# MTRduino_rev5_2.net
KiCad netlist of a schematic drawn in EAGLE
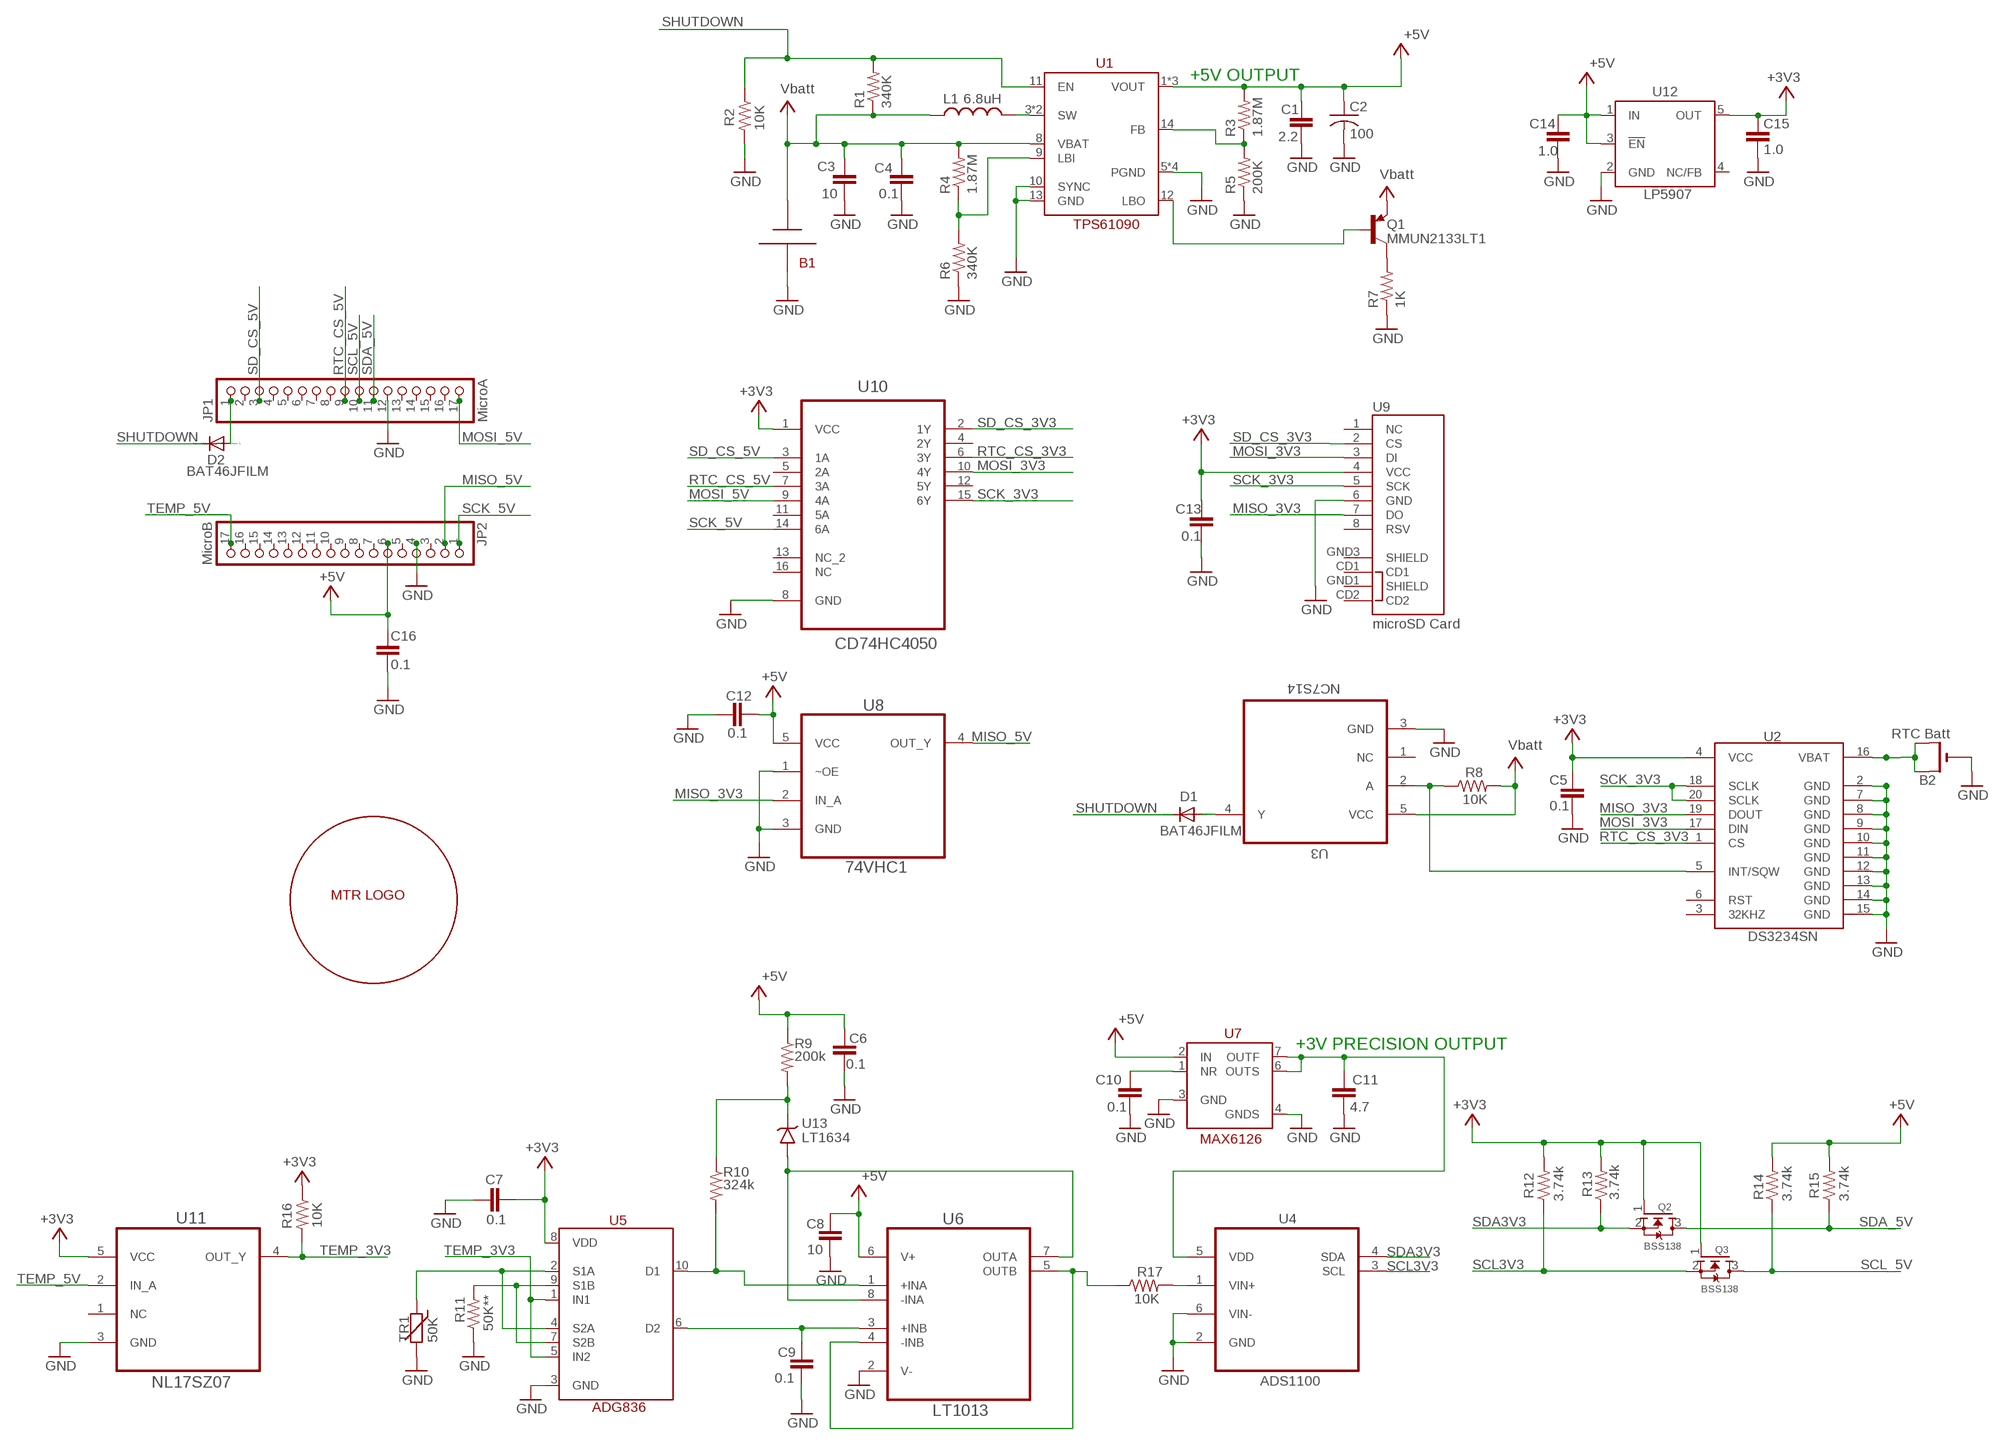
[diagram p0: schematic, sheet 1]

(export (version "E")
  (design (tool "Eeschema 10.0.6"))
  (components
    (comp (ref "B1")
      (value "2x AA BATT")
      (footprint "eagle-import:BATT_AA2")
      (libsource (lib "eagle-import") (part "BATT_AA2"))
    )
    (comp (ref "B2")
      (value "RTC Batt")
      (footprint "eagle-import:CR1220-SMD")
      (libsource (lib "eagle-import") (part "CR1220SMT"))
    )
    (comp (ref "C1")
      (value "2.2")
      (footprint "eagle-import:C0603")
      (libsource (lib "eagle-import") (part "C-EUC0603"))
    )
    (comp (ref "C2")
      (value "100")
      (footprint "eagle-import:C1206K")
      (libsource (lib "eagle-import") (part "C-USC1206K"))
    )
    (comp (ref "C3")
      (value "10")
      (footprint "eagle-import:C0603")
      (libsource (lib "eagle-import") (part "C-EUC0603"))
    )
    (comp (ref "C4")
      (value "0.1")
      (footprint "eagle-import:C0603")
      (libsource (lib "eagle-import") (part "C-EUC0603"))
    )
    (comp (ref "C5")
      (value "0.1")
      (footprint "eagle-import:C0603")
      (libsource (lib "eagle-import") (part "C-EUC0603"))
    )
    (comp (ref "C6")
      (value "0.1")
      (footprint "eagle-import:C0603")
      (libsource (lib "eagle-import") (part "C-EUC0603"))
    )
    (comp (ref "C7")
      (value "0.1")
      (footprint "eagle-import:C0603")
      (libsource (lib "eagle-import") (part "C-EUC0603"))
    )
    (comp (ref "C8")
      (value "10")
      (footprint "eagle-import:C0603")
      (libsource (lib "eagle-import") (part "C-EUC0603"))
    )
    (comp (ref "C9")
      (value "0.1")
      (footprint "eagle-import:C0603")
      (libsource (lib "eagle-import") (part "C-EUC0603"))
    )
    (comp (ref "C10")
      (value "0.1")
      (footprint "eagle-import:C0603")
      (libsource (lib "eagle-import") (part "C-EUC0603"))
    )
    (comp (ref "C11")
      (value "4.7")
      (footprint "eagle-import:C0603")
      (libsource (lib "eagle-import") (part "C-EUC0603"))
    )
    (comp (ref "C12")
      (value "0.1")
      (footprint "eagle-import:C0603")
      (libsource (lib "eagle-import") (part "C-EUC0603"))
    )
    (comp (ref "C13")
      (value "0.1")
      (footprint "eagle-import:C0603")
      (libsource (lib "eagle-import") (part "C-EUC0603"))
    )
    (comp (ref "C14")
      (value "1.0")
      (footprint "eagle-import:C0603")
      (libsource (lib "eagle-import") (part "C-EUC0603"))
    )
    (comp (ref "C15")
      (value "1.0")
      (footprint "eagle-import:C0603")
      (libsource (lib "eagle-import") (part "C-EUC0603"))
    )
    (comp (ref "C16")
      (value "0.1")
      (footprint "eagle-import:C0603")
      (libsource (lib "eagle-import") (part "C-EUC0603"))
    )
    (comp (ref "D1")
      (value "BAT46JFILM")
      (footprint "eagle-import:SOD323-R")
      (libsource (lib "eagle-import") (part "DIODE-SOD323-R"))
    )
    (comp (ref "D2")
      (value "BAT46JFILM")
      (footprint "eagle-import:SOD323-R")
      (libsource (lib "eagle-import") (part "DIODE-SOD323-R"))
    )
    (comp (ref "JP1")
      (value "MicroA")
      (footprint "eagle-import:1X17")
      (libsource (lib "eagle-import") (part "PINHD-1X17"))
    )
    (comp (ref "JP2")
      (value "MicroB")
      (footprint "eagle-import:1X17")
      (libsource (lib "eagle-import") (part "PINHD-1X17"))
    )
    (comp (ref "L1")
      (value "6.8uH")
      (footprint "eagle-import:VLC6045")
      (libsource (lib "eagle-import") (part "L-USVLC6045"))
    )
    (comp (ref "Q1")
      (value "MMUN2133LT1")
      (footprint "eagle-import:SC59-BEC")
      (libsource (lib "eagle-import") (part "MMUN2111LT1"))
    )
    (comp (ref "Q2")
      (value "BSS138")
      (footprint "eagle-import:SOT23")
      (libsource (lib "eagle-import") (part "MOSFET-NREFLOW"))
    )
    (comp (ref "Q3")
      (value "BSS138")
      (footprint "eagle-import:SOT23")
      (libsource (lib "eagle-import") (part "MOSFET-NREFLOW"))
    )
    (comp (ref "R1")
      (value "340K")
      (footprint "eagle-import:R0603")
      (libsource (lib "eagle-import") (part "R-US_R0603"))
    )
    (comp (ref "R2")
      (value "10K")
      (footprint "eagle-import:R0603")
      (libsource (lib "eagle-import") (part "R-US_R0603"))
    )
    (comp (ref "R3")
      (value "1.87M")
      (footprint "eagle-import:R0805")
      (libsource (lib "eagle-import") (part "R-US_R0805"))
    )
    (comp (ref "R4")
      (value "1.87M")
      (footprint "eagle-import:R0805")
      (libsource (lib "eagle-import") (part "R-US_R0805"))
    )
    (comp (ref "R5")
      (value "200K")
      (footprint "eagle-import:R0603")
      (libsource (lib "eagle-import") (part "R-US_R0603"))
    )
    (comp (ref "R6")
      (value "340K")
      (footprint "eagle-import:R0603")
      (libsource (lib "eagle-import") (part "R-US_R0603"))
    )
    (comp (ref "R7")
      (value "1K")
      (footprint "eagle-import:R0603")
      (libsource (lib "eagle-import") (part "R-US_R0603"))
    )
    (comp (ref "R8")
      (value "10K")
      (footprint "eagle-import:R0603")
      (libsource (lib "eagle-import") (part "R-US_R0603"))
    )
    (comp (ref "R9")
      (value "200k")
      (footprint "eagle-import:R1206")
      (libsource (lib "eagle-import") (part "R-US_R1206"))
    )
    (comp (ref "R10")
      (value "324k")
      (footprint "eagle-import:R1206")
      (libsource (lib "eagle-import") (part "R-US_R1206"))
    )
    (comp (ref "R11")
      (value "50K**")
      (footprint "eagle-import:R2010")
      (libsource (lib "eagle-import") (part "R-US_R2010"))
    )
    (comp (ref "R12")
      (value "3.74k")
      (footprint "eagle-import:R0603")
      (libsource (lib "eagle-import") (part "R-US_R0603"))
    )
    (comp (ref "R13")
      (value "3.74k")
      (footprint "eagle-import:R0603")
      (libsource (lib "eagle-import") (part "R-US_R0603"))
    )
    (comp (ref "R14")
      (value "3.74k")
      (footprint "eagle-import:R0603")
      (libsource (lib "eagle-import") (part "R-US_R0603"))
    )
    (comp (ref "R15")
      (value "3.74k")
      (footprint "eagle-import:R0603")
      (libsource (lib "eagle-import") (part "R-US_R0603"))
    )
    (comp (ref "R16")
      (value "10K")
      (footprint "eagle-import:R0603")
      (libsource (lib "eagle-import") (part "R-US_R0603"))
    )
    (comp (ref "R17")
      (value "10K")
      (footprint "eagle-import:R0603")
      (libsource (lib "eagle-import") (part "R-US_R0603"))
    )
    (comp (ref "TR1")
      (value "50K")
      (footprint "eagle-import:R-5")
      (libsource (lib "eagle-import") (part "THERMISTOR_R-5"))
    )
    (comp (ref "U$1")
      (value "MTRLOGO")
      (footprint "eagle-import:MTRLOGO")
      (libsource (lib "eagle-import") (part "MTRLOGO"))
    )
    (comp (ref "U1")
      (value "TPS61090")
      (footprint "eagle-import:QFN16-4X4")
      (libsource (lib "eagle-import") (part "TPS61090RSAR"))
    )
    (comp (ref "U2")
      (value "DS3234SN")
      (footprint "eagle-import:DS3234")
      (libsource (lib "eagle-import") (part "DS3234"))
    )
    (comp (ref "U3")
      (value "NC7S14")
      (footprint "eagle-import:SOT95P280X145-5N")
      (fields (field (name "MPN") "1P1G14MDBVREPG4"))
      (libsource (lib "eagle-import") (part "1P1G14MDBVREPG4"))
    )
    (comp (ref "U4")
      (value "ADS1100")
      (footprint "eagle-import:SOT95P280X145-6N")
      (fields (field (name "MPN") "ADS1100A0IDBVT"))
      (libsource (lib "eagle-import") (part "ADS1100A0IDBVT"))
    )
    (comp (ref "U5")
      (value "ADG836")
      (footprint "eagle-import:MSOP10")
      (libsource (lib "eagle-import") (part "ADG836"))
    )
    (comp (ref "U6")
      (value "LT1013")
      (footprint "eagle-import:SOIC127P600X175-8N")
      (fields (field (name "MPN") "LT1013DS8#PBF"))
      (libsource (lib "eagle-import") (part "LT1013DS8PBF"))
    )
    (comp (ref "U7")
      (value "MAX6126")
      (footprint "eagle-import:SOIC127P600X175-8N")
      (libsource (lib "eagle-import") (part "MAX6126"))
    )
    (comp (ref "U8")
      (value "74VHC1")
      (footprint "eagle-import:SOT65P210X110-5N")
      (fields (field (name "MPN") "M74VHC1GT125DF1G"))
      (libsource (lib "eagle-import") (part "M74VHC1GT125DF1G"))
    )
    (comp (ref "U9")
      (value "microSD Card")
      (footprint "eagle-import:MICROSD_1_1")
      (libsource (lib "eagle-import") (part "USD-SOCKET"))
    )
    (comp (ref "U10")
      (value "CD74HC4050")
      (footprint "eagle-import:SOIC127P600X175-16N")
      (fields (field (name "MPN") "M74HC4050RM13TR"))
      (libsource (lib "eagle-import") (part "M74HC4050RM13TR"))
    )
    (comp (ref "U11")
      (value "NL17SZ07")
      (footprint "eagle-import:SOT65P210X110-5N")
      (fields (field (name "MPN") "NL17SZ07DFT2G"))
      (libsource (lib "eagle-import") (part "NL17SZ07DFT2G"))
    )
    (comp (ref "U12")
      (value "LP5907")
      (footprint "eagle-import:SOT23-DBV")
      (fields (field (name "MF") "TEXAS INSTRUMENTS") (field (name "MPN") "TPS77030DBVT"))
      (libsource (lib "eagle-import") (part "TPS77030"))
    )
    (comp (ref "U13")
      (value "LT1634")
      (footprint "eagle-import:S8")
      (libsource (lib "eagle-import") (part "LT1634BIS8-1.25"))
    )
  )
  (nets
    (net (code "1") (name "+3V3") (class "Default")
      (node (ref "C13") (pin "1") (pinfunction "1_1") (pintype "passive"))
      (node (ref "C15") (pin "1") (pinfunction "1_1") (pintype "passive"))
      (node (ref "C5") (pin "1") (pinfunction "1_1") (pintype "passive"))
      (node (ref "C7") (pin "2") (pinfunction "2_2") (pintype "passive"))
      (node (ref "Q2") (pin "1") (pinfunction "G_1") (pintype "bidirectional"))
      (node (ref "Q3") (pin "1") (pinfunction "G_1") (pintype "bidirectional"))
      (node (ref "R12") (pin "2") (pinfunction "2_2") (pintype "passive"))
      (node (ref "R13") (pin "2") (pinfunction "2_2") (pintype "passive"))
      (node (ref "R16") (pin "1") (pinfunction "1_1") (pintype "passive"))
      (node (ref "U10") (pin "1") (pinfunction "VCC_1") (pintype "power_in"))
      (node (ref "U11") (pin "5") (pinfunction "VCC_5") (pintype "power_in"))
      (node (ref "U12") (pin "5") (pinfunction "OUT_5") (pintype "passive"))
      (node (ref "U2") (pin "4") (pinfunction "VCC_4") (pintype "bidirectional"))
      (node (ref "U5") (pin "8") (pinfunction "VDD_8") (pintype "bidirectional"))
      (node (ref "U9") (pin "4") (pinfunction "VCC_4") (pintype "bidirectional"))
    )
    (net (code "2") (name "+5V") (class "Default")
      (node (ref "C1") (pin "1") (pinfunction "1_1") (pintype "passive"))
      (node (ref "C12") (pin "1") (pinfunction "1_1") (pintype "passive"))
      (node (ref "C14") (pin "1") (pinfunction "1_1") (pintype "passive"))
      (node (ref "C16") (pin "1") (pinfunction "1_1") (pintype "passive"))
      (node (ref "C2") (pin "1") (pinfunction "1_1") (pintype "passive"))
      (node (ref "C6") (pin "2") (pinfunction "2_2") (pintype "passive"))
      (node (ref "C8") (pin "2") (pinfunction "2_2") (pintype "passive"))
      (node (ref "JP2") (pin "6") (pinfunction "6_6") (pintype "passive"))
      (node (ref "R14") (pin "2") (pinfunction "2_2") (pintype "passive"))
      (node (ref "R15") (pin "2") (pinfunction "2_2") (pintype "passive"))
      (node (ref "R3") (pin "2") (pinfunction "2_2") (pintype "passive"))
      (node (ref "R9") (pin "1") (pinfunction "1_1") (pintype "passive"))
      (node (ref "U1") (pin "1") (pinfunction "VOUT_1") (pintype "bidirectional"))
      (node (ref "U1") (pin "15") (pinfunction "VOUT_15") (pintype "bidirectional"))
      (node (ref "U1") (pin "16") (pinfunction "VOUT_16") (pintype "bidirectional"))
      (node (ref "U12") (pin "1") (pinfunction "IN_1") (pintype "input"))
      (node (ref "U12") (pin "3") (pinfunction "~{EN}_3") (pintype "input"))
      (node (ref "U6") (pin "6") (pinfunction "V+_6") (pintype "power_in"))
      (node (ref "U7") (pin "2") (pinfunction "IN_2") (pintype "input"))
      (node (ref "U8") (pin "5") (pinfunction "VCC_5") (pintype "power_in"))
    )
    (net (code "3") (name "/MISO_3V3") (class "Default")
      (node (ref "U2") (pin "19") (pinfunction "DOUT_19") (pintype "bidirectional"))
      (node (ref "U8") (pin "2") (pinfunction "IN_A_2") (pintype "input"))
      (node (ref "U9") (pin "7") (pinfunction "DO_7") (pintype "bidirectional"))
    )
    (net (code "4") (name "/MISO_5V") (class "Default")
      (node (ref "JP2") (pin "2") (pinfunction "2_2") (pintype "passive"))
      (node (ref "U8") (pin "4") (pinfunction "OUT_Y_4") (pintype "output"))
    )
    (net (code "5") (name "/MOSI_3V3") (class "Default")
      (node (ref "U10") (pin "10") (pinfunction "4Y_10") (pintype "output"))
      (node (ref "U2") (pin "17") (pinfunction "DIN_17") (pintype "bidirectional"))
      (node (ref "U9") (pin "3") (pinfunction "DI_3") (pintype "bidirectional"))
    )
    (net (code "6") (name "/MOSI_5V") (class "Default")
      (node (ref "JP1") (pin "17") (pinfunction "17_17") (pintype "passive"))
      (node (ref "U10") (pin "9") (pinfunction "4A_9") (pintype "input"))
    )
    (net (code "7") (name "/RTC_CS_3V3") (class "Default")
      (node (ref "U10") (pin "6") (pinfunction "3Y_6") (pintype "output"))
      (node (ref "U2") (pin "1") (pinfunction "CS_1") (pintype "bidirectional"))
    )
    (net (code "8") (name "/RTC_CS_5V") (class "Default")
      (node (ref "JP1") (pin "9") (pinfunction "9_9") (pintype "passive"))
      (node (ref "U10") (pin "7") (pinfunction "3A_7") (pintype "input"))
    )
    (net (code "9") (name "/SCK_3V3") (class "Default")
      (node (ref "U10") (pin "15") (pinfunction "6Y_15") (pintype "output"))
      (node (ref "U2") (pin "18") (pinfunction "SCLK_18") (pintype "bidirectional"))
      (node (ref "U2") (pin "20") (pinfunction "SCLK_20") (pintype "bidirectional"))
      (node (ref "U9") (pin "5") (pinfunction "SCK_5") (pintype "bidirectional"))
    )
    (net (code "10") (name "/SCK_5V") (class "Default")
      (node (ref "JP2") (pin "1") (pinfunction "1_1") (pintype "passive"))
      (node (ref "U10") (pin "14") (pinfunction "6A_14") (pintype "input"))
    )
    (net (code "11") (name "/SCL3V3") (class "Default")
      (node (ref "Q3") (pin "2") (pinfunction "S_2") (pintype "bidirectional"))
      (node (ref "R12") (pin "1") (pinfunction "1_1") (pintype "passive"))
      (node (ref "U4") (pin "3") (pinfunction "SCL_3") (pintype "output"))
    )
    (net (code "12") (name "/SCL_5V") (class "Default")
      (node (ref "JP1") (pin "10") (pinfunction "10_10") (pintype "passive"))
      (node (ref "Q3") (pin "3") (pinfunction "D_3") (pintype "bidirectional"))
      (node (ref "R14") (pin "1") (pinfunction "1_1") (pintype "passive"))
    )
    (net (code "13") (name "/SDA3V3") (class "Default")
      (node (ref "Q2") (pin "2") (pinfunction "S_2") (pintype "bidirectional"))
      (node (ref "R13") (pin "1") (pinfunction "1_1") (pintype "passive"))
      (node (ref "U4") (pin "4") (pinfunction "SDA_4") (pintype "output"))
    )
    (net (code "14") (name "/SDA_5V") (class "Default")
      (node (ref "JP1") (pin "11") (pinfunction "11_11") (pintype "passive"))
      (node (ref "Q2") (pin "3") (pinfunction "D_3") (pintype "bidirectional"))
      (node (ref "R15") (pin "1") (pinfunction "1_1") (pintype "passive"))
    )
    (net (code "15") (name "/SD_CS_3V3") (class "Default")
      (node (ref "U10") (pin "2") (pinfunction "1Y_2") (pintype "output"))
      (node (ref "U9") (pin "2") (pinfunction "CS_2") (pintype "bidirectional"))
    )
    (net (code "16") (name "/SD_CS_5V") (class "Default")
      (node (ref "JP1") (pin "3") (pinfunction "3_3") (pintype "passive"))
      (node (ref "U10") (pin "3") (pinfunction "1A_3") (pintype "input"))
    )
    (net (code "17") (name "/SHUTDOWN") (class "Default")
      (node (ref "D1") (pin "C") (pinfunction "C_C") (pintype "passive"))
      (node (ref "D2") (pin "C") (pinfunction "C_C") (pintype "passive"))
      (node (ref "R1") (pin "2") (pinfunction "2_2") (pintype "passive"))
      (node (ref "R2") (pin "1") (pinfunction "1_1") (pintype "passive"))
      (node (ref "U1") (pin "11") (pinfunction "EN_11") (pintype "bidirectional"))
    )
    (net (code "18") (name "/TEMP_3V3") (class "Default")
      (node (ref "R16") (pin "2") (pinfunction "2_2") (pintype "passive"))
      (node (ref "U11") (pin "4") (pinfunction "OUT_Y_4") (pintype "output"))
      (node (ref "U5") (pin "1") (pinfunction "IN1_1") (pintype "bidirectional"))
      (node (ref "U5") (pin "5") (pinfunction "IN2_5") (pintype "bidirectional"))
    )
    (net (code "19") (name "/TEMP_5V") (class "Default")
      (node (ref "JP2") (pin "17") (pinfunction "17_17") (pintype "passive"))
      (node (ref "U11") (pin "2") (pinfunction "IN_A_2") (pintype "input"))
    )
    (net (code "20") (name "GND") (class "Default")
      (node (ref "B1") (pin "-") (pinfunction "+_-") (pintype "bidirectional"))
      (node (ref "B2") (pin "-") (pinfunction "-_-") (pintype "passive"))
      (node (ref "C1") (pin "2") (pinfunction "2_2") (pintype "passive"))
      (node (ref "C10") (pin "2") (pinfunction "2_2") (pintype "passive"))
      (node (ref "C11") (pin "2") (pinfunction "2_2") (pintype "passive"))
      (node (ref "C12") (pin "2") (pinfunction "2_2") (pintype "passive"))
      (node (ref "C13") (pin "2") (pinfunction "2_2") (pintype "passive"))
      (node (ref "C14") (pin "2") (pinfunction "2_2") (pintype "passive"))
      (node (ref "C15") (pin "2") (pinfunction "2_2") (pintype "passive"))
      (node (ref "C16") (pin "2") (pinfunction "2_2") (pintype "passive"))
      (node (ref "C2") (pin "2") (pinfunction "2_2") (pintype "passive"))
      (node (ref "C3") (pin "2") (pinfunction "2_2") (pintype "passive"))
      (node (ref "C4") (pin "2") (pinfunction "2_2") (pintype "passive"))
      (node (ref "C5") (pin "2") (pinfunction "2_2") (pintype "passive"))
      (node (ref "C6") (pin "1") (pinfunction "1_1") (pintype "passive"))
      (node (ref "C7") (pin "1") (pinfunction "1_1") (pintype "passive"))
      (node (ref "C8") (pin "1") (pinfunction "1_1") (pintype "passive"))
      (node (ref "C9") (pin "1") (pinfunction "1_1") (pintype "passive"))
      (node (ref "JP1") (pin "12") (pinfunction "12_12") (pintype "passive"))
      (node (ref "JP2") (pin "4") (pinfunction "4_4") (pintype "passive"))
      (node (ref "R11") (pin "1") (pinfunction "1_1") (pintype "passive"))
      (node (ref "R2") (pin "2") (pinfunction "2_2") (pintype "passive"))
      (node (ref "R5") (pin "1") (pinfunction "1_1") (pintype "passive"))
      (node (ref "R6") (pin "1") (pinfunction "1_1") (pintype "passive"))
      (node (ref "R7") (pin "1") (pinfunction "1_1") (pintype "passive"))
      (node (ref "TR1") (pin "2") (pinfunction "2_2") (pintype "passive"))
      (node (ref "U1") (pin "10") (pinfunction "SYNC_10") (pintype "bidirectional"))
      (node (ref "U1") (pin "13") (pinfunction "GND_13") (pintype "bidirectional"))
      (node (ref "U1") (pin "5") (pinfunction "PGND_5") (pintype "bidirectional"))
      (node (ref "U1") (pin "6") (pinfunction "PGND_6") (pintype "bidirectional"))
      (node (ref "U1") (pin "7") (pinfunction "PGND_7") (pintype "bidirectional"))
      (node (ref "U1") (pin "EXP") (pinfunction "PGND_EXP") (pintype "bidirectional"))
      (node (ref "U10") (pin "8") (pinfunction "GND_8") (pintype "passive"))
      (node (ref "U11") (pin "3") (pinfunction "GND_3") (pintype "passive"))
      (node (ref "U12") (pin "2") (pinfunction "GND_2") (pintype "power_in"))
      (node (ref "U2") (pin "10") (pinfunction "GND_10") (pintype "bidirectional"))
      (node (ref "U2") (pin "11") (pinfunction "GND_11") (pintype "bidirectional"))
      (node (ref "U2") (pin "12") (pinfunction "GND_12") (pintype "bidirectional"))
      (node (ref "U2") (pin "13") (pinfunction "GND_13") (pintype "bidirectional"))
      (node (ref "U2") (pin "14") (pinfunction "GND_14") (pintype "bidirectional"))
      (node (ref "U2") (pin "15") (pinfunction "GND_15") (pintype "bidirectional"))
      (node (ref "U2") (pin "2") (pinfunction "GND_2") (pintype "bidirectional"))
      (node (ref "U2") (pin "7") (pinfunction "GND_7") (pintype "bidirectional"))
      (node (ref "U2") (pin "8") (pinfunction "GND_8") (pintype "bidirectional"))
      (node (ref "U2") (pin "9") (pinfunction "GND_9") (pintype "bidirectional"))
      (node (ref "U3") (pin "3") (pinfunction "GND_3") (pintype "passive"))
      (node (ref "U4") (pin "2") (pinfunction "GND_2") (pintype "passive"))
      (node (ref "U4") (pin "6") (pinfunction "VIN-_6") (pintype "input"))
      (node (ref "U5") (pin "3") (pinfunction "GND_3") (pintype "bidirectional"))
      (node (ref "U6") (pin "2") (pinfunction "V-_2") (pintype "power_in"))
      (node (ref "U7") (pin "3") (pinfunction "GND_3") (pintype "input"))
      (node (ref "U7") (pin "4") (pinfunction "GNDS_4") (pintype "input"))
      (node (ref "U8") (pin "1") (pinfunction "~{OE}_1") (pintype "input"))
      (node (ref "U8") (pin "3") (pinfunction "GND_3") (pintype "passive"))
      (node (ref "U9") (pin "6") (pinfunction "GND_6") (pintype "bidirectional"))
    )
    (net (code "21") (name "Net-(B2-+)") (class "Default")
      (node (ref "B2") (pin "+$1") (pinfunction "+_+$1") (pintype "passive"))
      (node (ref "B2") (pin "+$2") (pinfunction "+1_+$2") (pintype "passive"))
      (node (ref "U2") (pin "16") (pinfunction "VBAT_16") (pintype "bidirectional"))
    )
    (net (code "22") (name "Net-(D2-PadA)") (class "Default")
      (node (ref "D2") (pin "A") (pinfunction "A_A") (pintype "passive"))
      (node (ref "JP1") (pin "1") (pinfunction "1_1") (pintype "passive"))
    )
    (net (code "23") (name "Net-(L1-2)") (class "Default")
      (node (ref "L1") (pin "P$3") (pinfunction "2_P$3") (pintype "passive"))
      (node (ref "U1") (pin "3") (pinfunction "SW_3") (pintype "bidirectional"))
      (node (ref "U1") (pin "4") (pinfunction "SW_4") (pintype "bidirectional"))
    )
    (net (code "24") (name "Net-(Q1-PadC)") (class "Default")
      (node (ref "Q1") (pin "C") (pinfunction "C_C") (pintype "passive"))
      (node (ref "R7") (pin "2") (pinfunction "2_2") (pintype "passive"))
    )
    (net (code "25") (name "Net-(U1-FB)") (class "Default")
      (node (ref "R3") (pin "1") (pinfunction "1_1") (pintype "passive"))
      (node (ref "R5") (pin "2") (pinfunction "2_2") (pintype "passive"))
      (node (ref "U1") (pin "14") (pinfunction "FB_14") (pintype "bidirectional"))
    )
    (net (code "26") (name "Net-(U1-LBI)") (class "Default")
      (node (ref "R4") (pin "1") (pinfunction "1_1") (pintype "passive"))
      (node (ref "R6") (pin "2") (pinfunction "2_2") (pintype "passive"))
      (node (ref "U1") (pin "9") (pinfunction "LBI_9") (pintype "bidirectional"))
    )
    (net (code "27") (name "Net-(U1-LBO)") (class "Default")
      (node (ref "Q1") (pin "B") (pinfunction "B_B") (pintype "passive"))
      (node (ref "U1") (pin "12") (pinfunction "LBO_12") (pintype "bidirectional"))
    )
    (net (code "28") (name "Net-(U2-INT{slash}SQW)") (class "Default")
      (node (ref "R8") (pin "1") (pinfunction "1_1") (pintype "passive"))
      (node (ref "U2") (pin "5") (pinfunction "INT/SQW_5") (pintype "bidirectional"))
      (node (ref "U3") (pin "2") (pinfunction "A_2") (pintype "input"))
    )
    (net (code "29") (name "Net-(U3-Y)") (class "Default")
      (node (ref "D1") (pin "A") (pinfunction "A_A") (pintype "passive"))
      (node (ref "U3") (pin "4") (pinfunction "Y_4") (pintype "output"))
    )
    (net (code "30") (name "Net-(U4-VDD)") (class "Default")
      (node (ref "C11") (pin "1") (pinfunction "1_1") (pintype "passive"))
      (node (ref "U4") (pin "5") (pinfunction "VDD_5") (pintype "power_in"))
      (node (ref "U7") (pin "6") (pinfunction "OUTS_6") (pintype "output"))
      (node (ref "U7") (pin "7") (pinfunction "OUTF_7") (pintype "output"))
    )
    (net (code "31") (name "Net-(U4-VIN+)") (class "Default")
      (node (ref "R17") (pin "2") (pinfunction "2_2") (pintype "passive"))
      (node (ref "U4") (pin "1") (pinfunction "VIN+_1") (pintype "input"))
    )
    (net (code "32") (name "Net-(U5-D1)") (class "Default")
      (node (ref "R10") (pin "2") (pinfunction "2_2") (pintype "passive"))
      (node (ref "U5") (pin "10") (pinfunction "D1_10") (pintype "bidirectional"))
      (node (ref "U6") (pin "1") (pinfunction "+INA_1") (pintype "input"))
    )
    (net (code "33") (name "Net-(U5-D2)") (class "Default")
      (node (ref "C9") (pin "2") (pinfunction "2_2") (pintype "passive"))
      (node (ref "U5") (pin "6") (pinfunction "D2_6") (pintype "bidirectional"))
      (node (ref "U6") (pin "3") (pinfunction "+INB_3") (pintype "input"))
    )
    (net (code "34") (name "Net-(U5-S1A)") (class "Default")
      (node (ref "TR1") (pin "1") (pinfunction "1_1") (pintype "passive"))
      (node (ref "U5") (pin "2") (pinfunction "S1A_2") (pintype "bidirectional"))
      (node (ref "U5") (pin "4") (pinfunction "S2A_4") (pintype "bidirectional"))
    )
    (net (code "35") (name "Net-(U5-S1B)") (class "Default")
      (node (ref "R11") (pin "2") (pinfunction "2_2") (pintype "passive"))
      (node (ref "U5") (pin "7") (pinfunction "S2B_7") (pintype "bidirectional"))
      (node (ref "U5") (pin "9") (pinfunction "S1B_9") (pintype "bidirectional"))
    )
    (net (code "36") (name "Net-(U6--INB)") (class "Default")
      (node (ref "R17") (pin "1") (pinfunction "1_1") (pintype "passive"))
      (node (ref "U6") (pin "4") (pinfunction "-INB_4") (pintype "input"))
      (node (ref "U6") (pin "5") (pinfunction "OUTB_5") (pintype "output"))
    )
    (net (code "37") (name "Net-(U7-NR)") (class "Default")
      (node (ref "C10") (pin "1") (pinfunction "1_1") (pintype "passive"))
      (node (ref "U7") (pin "1") (pinfunction "NR_1") (pintype "bidirectional"))
    )
    (net (code "38") (name "Net-(U13-GND)") (class "Default")
      (node (ref "U13") (pin "4") (pinfunction "GND_4") (pintype "passive"))
      (node (ref "U6") (pin "7") (pinfunction "OUTA_7") (pintype "output"))
      (node (ref "U6") (pin "8") (pinfunction "-INA_8") (pintype "input"))
    )
    (net (code "39") (name "Net-(U13-VOUT)") (class "Default")
      (node (ref "R10") (pin "1") (pinfunction "1_1") (pintype "passive"))
      (node (ref "R9") (pin "2") (pinfunction "2_2") (pintype "passive"))
      (node (ref "U13") (pin "6") (pinfunction "VOUT_6") (pintype "passive"))
    )
    (net (code "40") (name "Vbatt") (class "Default")
      (node (ref "B1") (pin "+") (pinfunction "-_+") (pintype "bidirectional"))
      (node (ref "C3") (pin "1") (pinfunction "1_1") (pintype "passive"))
      (node (ref "C4") (pin "1") (pinfunction "1_1") (pintype "passive"))
      (node (ref "L1") (pin "P$2") (pinfunction "1_P$2") (pintype "passive"))
      (node (ref "Q1") (pin "E") (pinfunction "E_E") (pintype "passive"))
      (node (ref "R1") (pin "1") (pinfunction "1_1") (pintype "passive"))
      (node (ref "R4") (pin "2") (pinfunction "2_2") (pintype "passive"))
      (node (ref "R8") (pin "2") (pinfunction "2_2") (pintype "passive"))
      (node (ref "U1") (pin "8") (pinfunction "VBAT_8") (pintype "bidirectional"))
      (node (ref "U3") (pin "5") (pinfunction "VCC_5") (pintype "power_in"))
    )
    (net (code "41") (name "unconnected-(JP1-Pad2)") (class "Default")
      (node (ref "JP1") (pin "2") (pinfunction "2_2") (pintype "passive"))
    )
    (net (code "42") (name "unconnected-(JP1-Pad4)") (class "Default")
      (node (ref "JP1") (pin "4") (pinfunction "4_4") (pintype "passive"))
    )
    (net (code "43") (name "unconnected-(JP1-Pad5)") (class "Default")
      (node (ref "JP1") (pin "5") (pinfunction "5_5") (pintype "passive"))
    )
    (net (code "44") (name "unconnected-(JP1-Pad6)") (class "Default")
      (node (ref "JP1") (pin "6") (pinfunction "6_6") (pintype "passive"))
    )
    (net (code "45") (name "unconnected-(JP1-Pad7)") (class "Default")
      (node (ref "JP1") (pin "7") (pinfunction "7_7") (pintype "passive"))
    )
    (net (code "46") (name "unconnected-(JP1-Pad8)") (class "Default")
      (node (ref "JP1") (pin "8") (pinfunction "8_8") (pintype "passive"))
    )
    (net (code "47") (name "unconnected-(JP1-Pad13)") (class "Default")
      (node (ref "JP1") (pin "13") (pinfunction "13_13") (pintype "passive"))
    )
    (net (code "48") (name "unconnected-(JP1-Pad14)") (class "Default")
      (node (ref "JP1") (pin "14") (pinfunction "14_14") (pintype "passive"))
    )
    (net (code "49") (name "unconnected-(JP1-Pad15)") (class "Default")
      (node (ref "JP1") (pin "15") (pinfunction "15_15") (pintype "passive"))
    )
    (net (code "50") (name "unconnected-(JP1-Pad16)") (class "Default")
      (node (ref "JP1") (pin "16") (pinfunction "16_16") (pintype "passive"))
    )
    (net (code "51") (name "unconnected-(JP2-Pad3)") (class "Default")
      (node (ref "JP2") (pin "3") (pinfunction "3_3") (pintype "passive"))
    )
    (net (code "52") (name "unconnected-(JP2-Pad5)") (class "Default")
      (node (ref "JP2") (pin "5") (pinfunction "5_5") (pintype "passive"))
    )
    (net (code "53") (name "unconnected-(JP2-Pad7)") (class "Default")
      (node (ref "JP2") (pin "7") (pinfunction "7_7") (pintype "passive"))
    )
    (net (code "54") (name "unconnected-(JP2-Pad8)") (class "Default")
      (node (ref "JP2") (pin "8") (pinfunction "8_8") (pintype "passive"))
    )
    (net (code "55") (name "unconnected-(JP2-Pad9)") (class "Default")
      (node (ref "JP2") (pin "9") (pinfunction "9_9") (pintype "passive"))
    )
    (net (code "56") (name "unconnected-(JP2-Pad10)") (class "Default")
      (node (ref "JP2") (pin "10") (pinfunction "10_10") (pintype "passive"))
    )
    (net (code "57") (name "unconnected-(JP2-Pad11)") (class "Default")
      (node (ref "JP2") (pin "11") (pinfunction "11_11") (pintype "passive"))
    )
    (net (code "58") (name "unconnected-(JP2-Pad12)") (class "Default")
      (node (ref "JP2") (pin "12") (pinfunction "12_12") (pintype "passive"))
    )
    (net (code "59") (name "unconnected-(JP2-Pad13)") (class "Default")
      (node (ref "JP2") (pin "13") (pinfunction "13_13") (pintype "passive"))
    )
    (net (code "60") (name "unconnected-(JP2-Pad14)") (class "Default")
      (node (ref "JP2") (pin "14") (pinfunction "14_14") (pintype "passive"))
    )
    (net (code "61") (name "unconnected-(JP2-Pad15)") (class "Default")
      (node (ref "JP2") (pin "15") (pinfunction "15_15") (pintype "passive"))
    )
    (net (code "62") (name "unconnected-(JP2-Pad16)") (class "Default")
      (node (ref "JP2") (pin "16") (pinfunction "16_16") (pintype "passive"))
    )
    (net (code "63") (name "unconnected-(U2-32KHZ-Pad3)") (class "Default")
      (node (ref "U2") (pin "3") (pinfunction "32KHZ_3") (pintype "bidirectional"))
    )
    (net (code "64") (name "unconnected-(U2-RST-Pad6)") (class "Default")
      (node (ref "U2") (pin "6") (pinfunction "RST_6") (pintype "bidirectional"))
    )
    (net (code "65") (name "unconnected-(U3-NC-Pad1)") (class "Default")
      (node (ref "U3") (pin "1") (pinfunction "NC_1") (pintype "no_connect"))
    )
    (net (code "66") (name "unconnected-(U9-NC-Pad1)") (class "Default")
      (node (ref "U9") (pin "1") (pinfunction "NC_1") (pintype "bidirectional"))
    )
    (net (code "67") (name "unconnected-(U9-PadCD1)") (class "Default")
      (node (ref "U9") (pin "CD1") (pinfunction "CD1_CD1") (pintype "bidirectional"))
    )
    (net (code "68") (name "unconnected-(U9-PadCD2)") (class "Default")
      (node (ref "U9") (pin "CD2") (pinfunction "CD2_CD2") (pintype "bidirectional"))
    )
    (net (code "69") (name "unconnected-(U9-RSV-Pad8)") (class "Default")
      (node (ref "U9") (pin "8") (pinfunction "RSV_8") (pintype "bidirectional"))
    )
    (net (code "70") (name "unconnected-(U9-SHIELD-PadGND1)") (class "Default")
      (node (ref "U9") (pin "GND1") (pinfunction "SHIELD_GND1") (pintype "bidirectional"))
    )
    (net (code "71") (name "unconnected-(U9-SHIELD-PadGND3)") (class "Default")
      (node (ref "U9") (pin "GND3") (pinfunction "SHIELD_GND3") (pintype "bidirectional"))
    )
    (net (code "72") (name "unconnected-(U10-2A-Pad5)") (class "Default")
      (node (ref "U10") (pin "5") (pinfunction "2A_5") (pintype "input"))
    )
    (net (code "73") (name "unconnected-(U10-2Y-Pad4)") (class "Default")
      (node (ref "U10") (pin "4") (pinfunction "2Y_4") (pintype "output"))
    )
    (net (code "74") (name "unconnected-(U10-5A-Pad11)") (class "Default")
      (node (ref "U10") (pin "11") (pinfunction "5A_11") (pintype "input"))
    )
    (net (code "75") (name "unconnected-(U10-5Y-Pad12)") (class "Default")
      (node (ref "U10") (pin "12") (pinfunction "5Y_12") (pintype "output"))
    )
    (net (code "76") (name "unconnected-(U10-NC-Pad16)") (class "Default")
      (node (ref "U10") (pin "16") (pinfunction "NC_16") (pintype "no_connect"))
    )
    (net (code "77") (name "unconnected-(U10-NC_2-Pad13)") (class "Default")
      (node (ref "U10") (pin "13") (pinfunction "NC_2_13") (pintype "no_connect"))
    )
    (net (code "78") (name "unconnected-(U11-NC-Pad1)") (class "Default")
      (node (ref "U11") (pin "1") (pinfunction "NC_1") (pintype "no_connect"))
    )
    (net (code "79") (name "unconnected-(U12-NC{slash}FB-Pad4)") (class "Default")
      (node (ref "U12") (pin "4") (pinfunction "NC/FB_4") (pintype "passive"))
    )
  )
)
